# GPSGSMTruck.net
KiCad netlist of a schematic drawn in Altium Designer
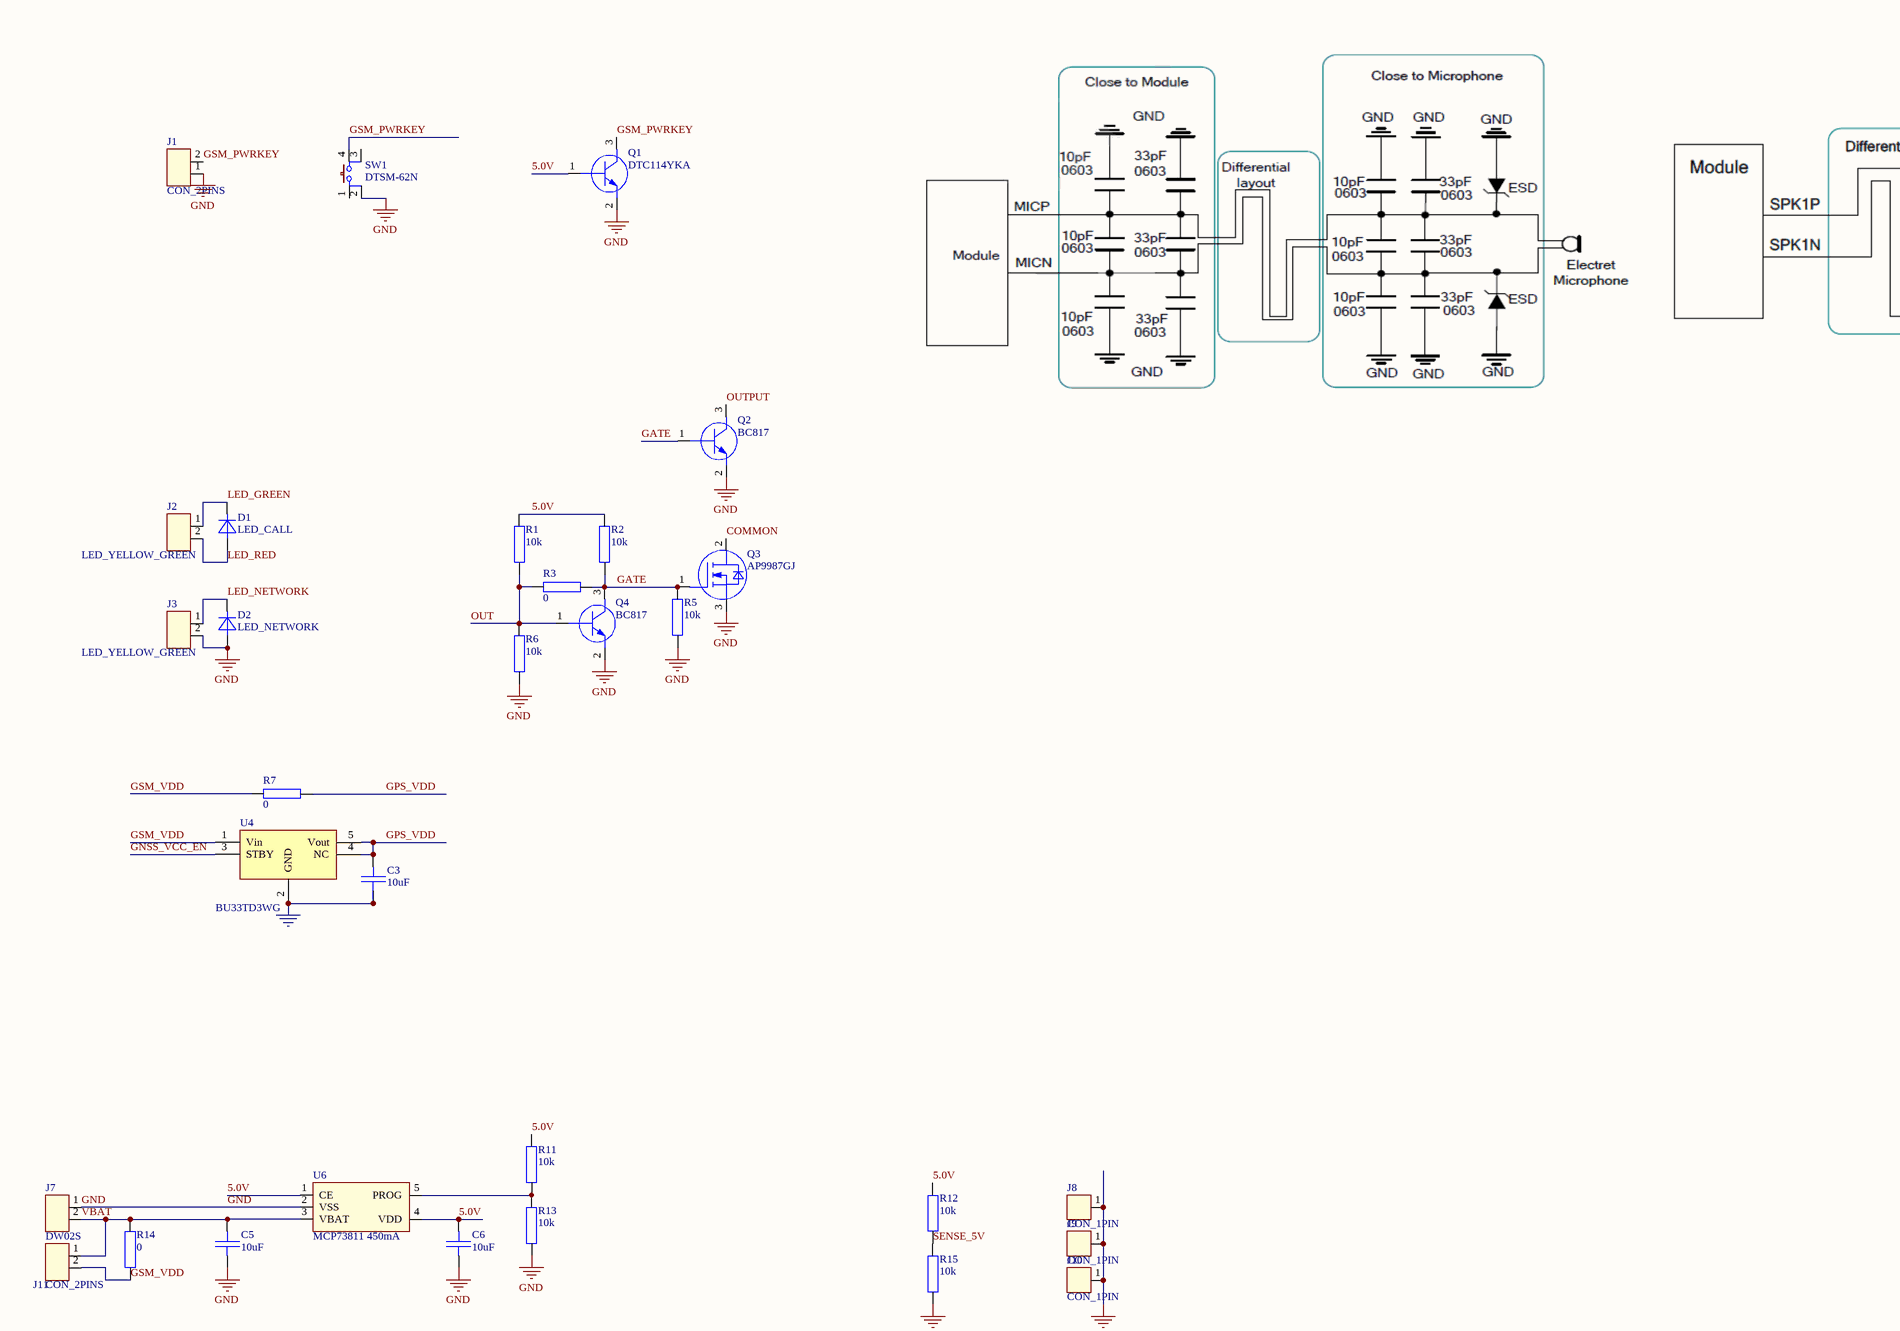
[diagram p0: GPSGSMTruck.SchDoc, top left]
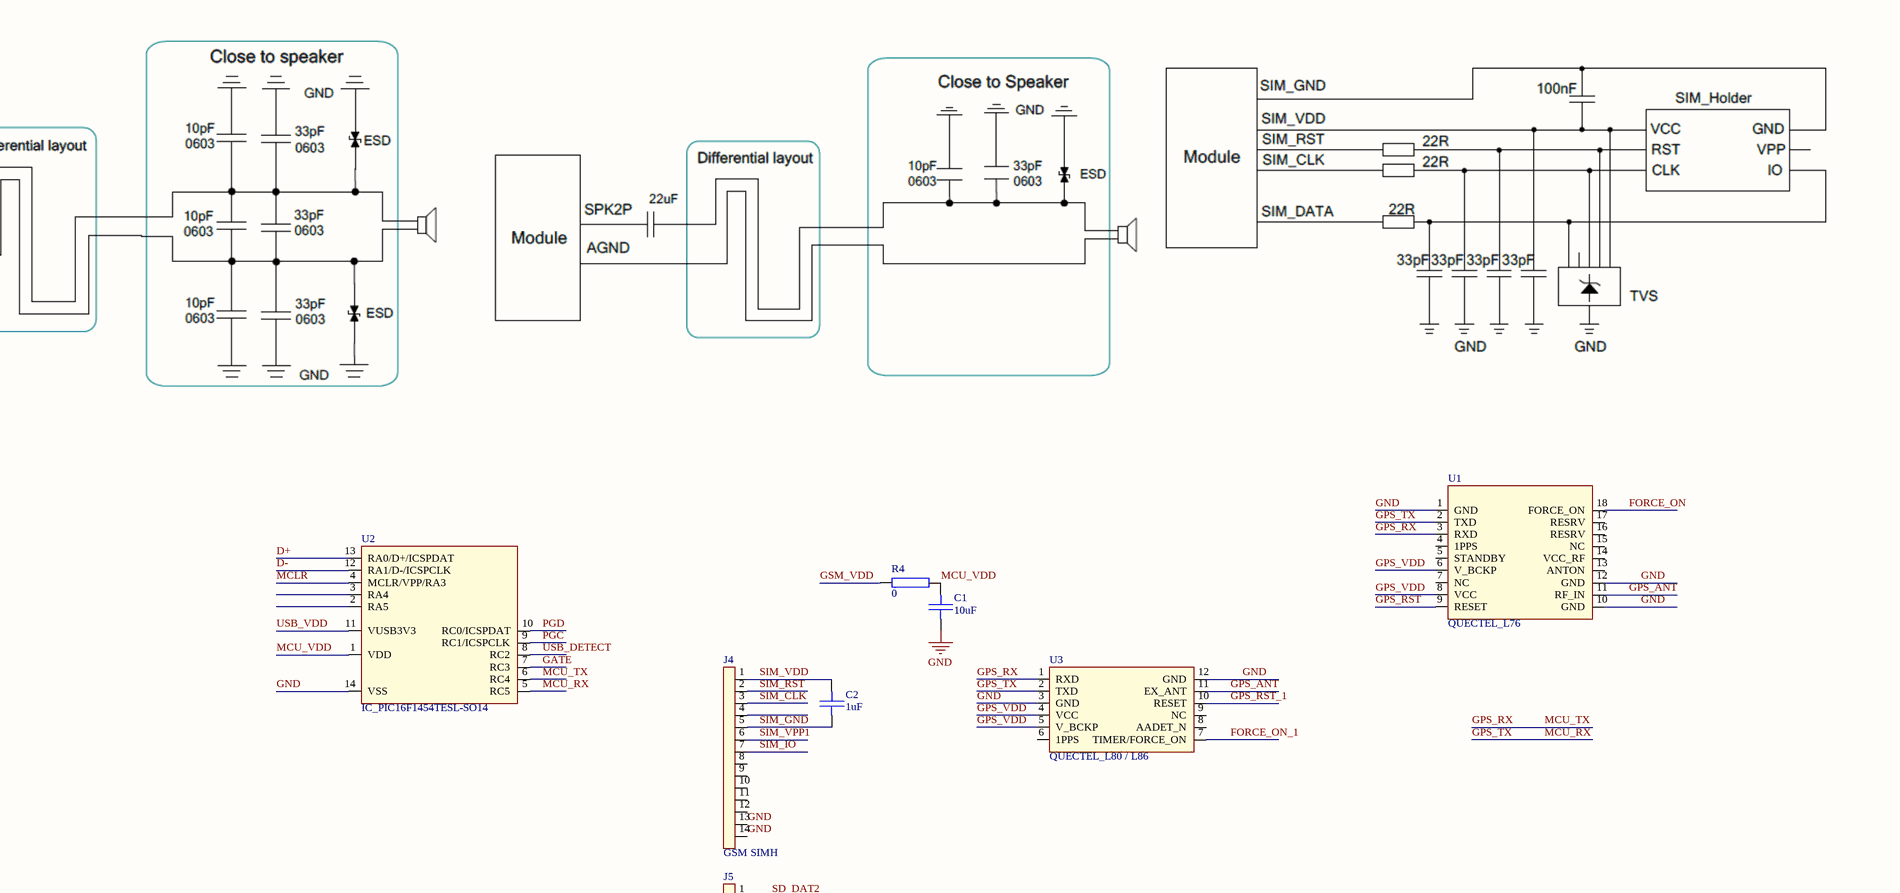
[diagram p1: GPSGSMTruck.SchDoc, top right]
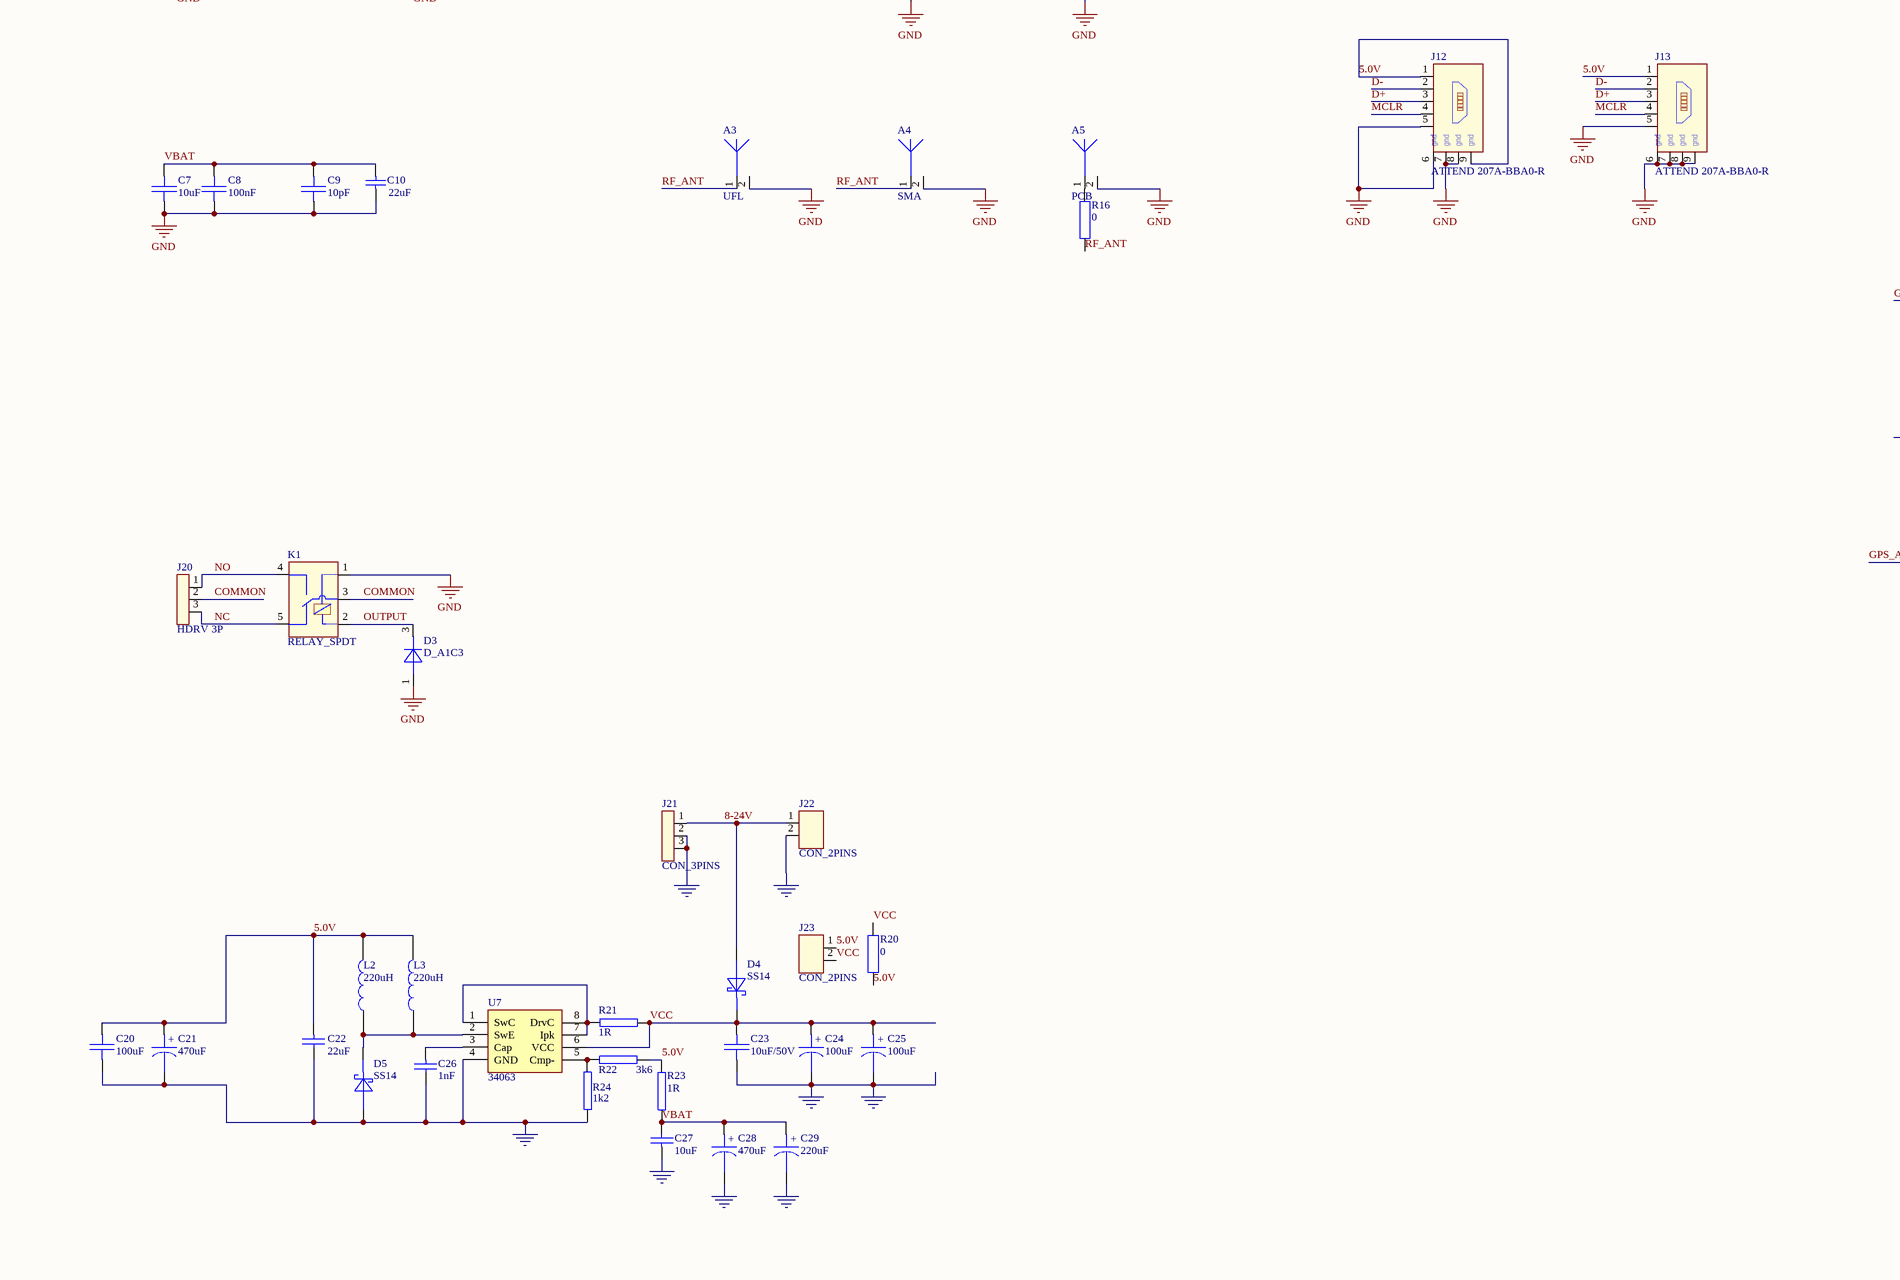
[diagram p2: GPSGSMTruck.SchDoc, bottom left]
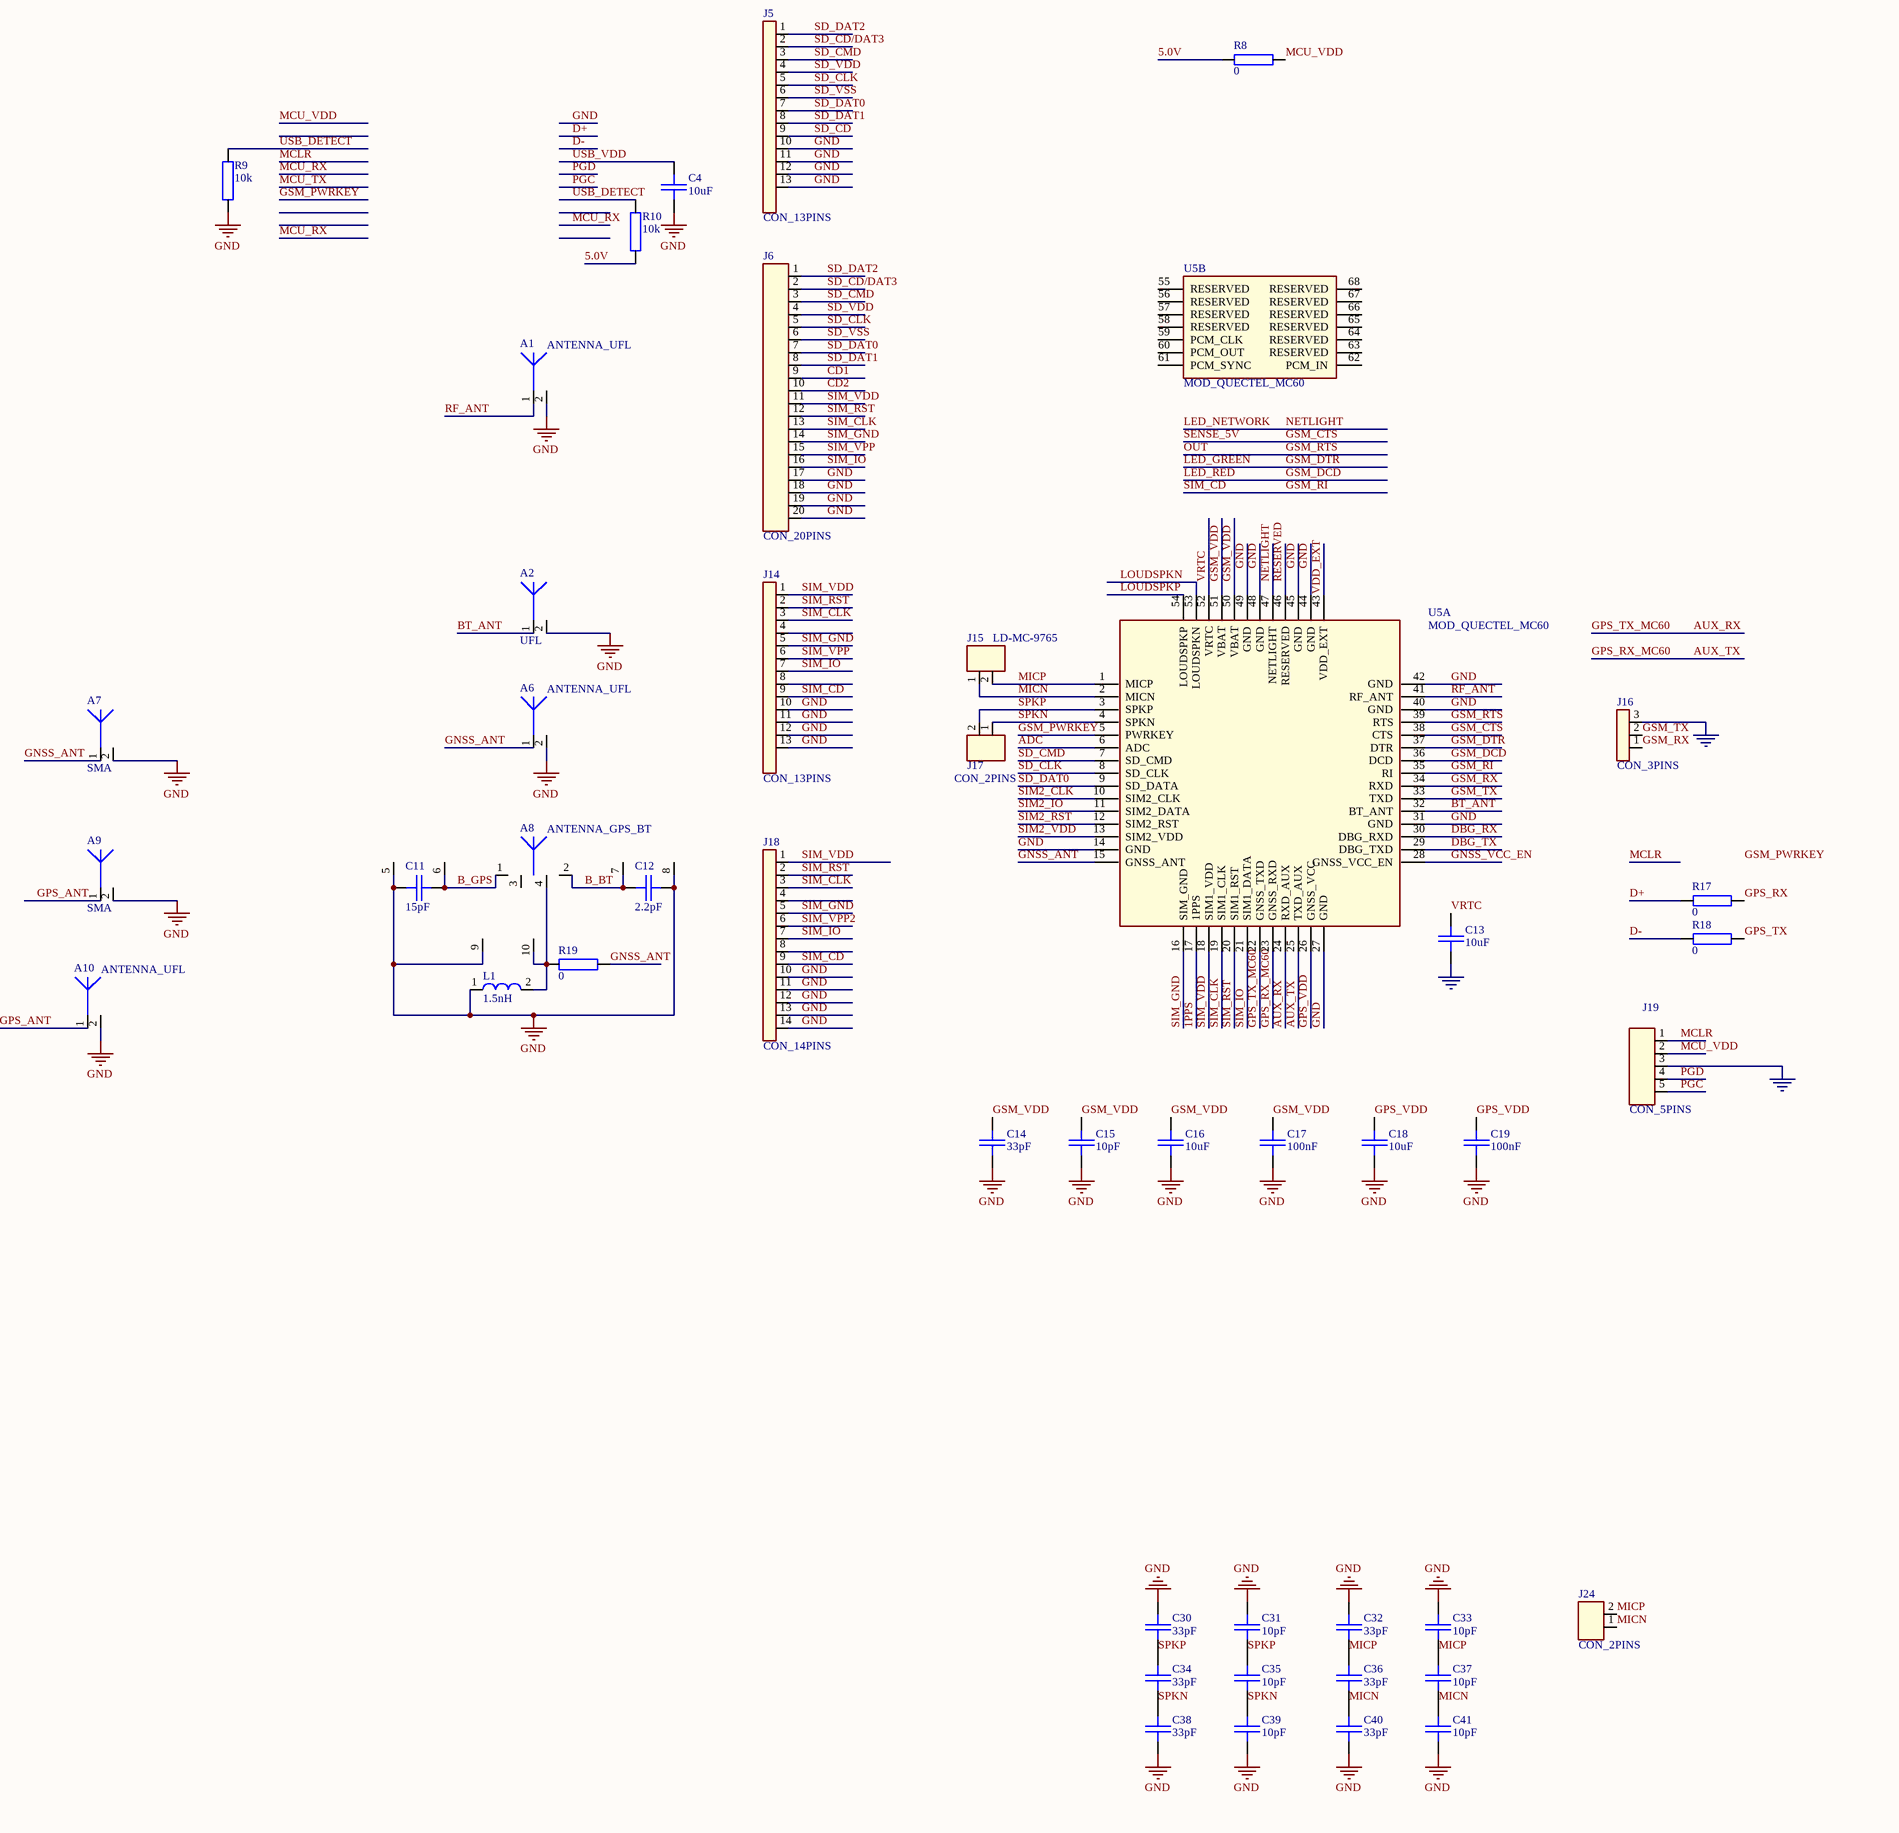
[diagram p3: GPSGSMTruck.SchDoc, bottom right]

(export (version "E")
  (design (tool "Eeschema 10.0.6"))
  (components
    (comp (ref "A1")
      (value "ANTENNA_UFL")
      (footprint "SMD_CON_ANTENNA_UFL")
      (libsource (lib "DLV") (part "ANTENNA_2"))
    )
    (comp (ref "A2")
      (value "UFL")
      (footprint "SMD_CON_ANTENNA_UFL")
      (libsource (lib "DLV") (part "ANTENNA_2"))
    )
    (comp (ref "A3")
      (value "UFL")
      (footprint "SMD_CON_ANTENNA_UFL")
      (libsource (lib "DLV") (part "ANTENNA_2"))
    )
    (comp (ref "A4")
      (value "SMA")
      (footprint "SMD_CON_ANTENNA_SMA_RIGHT_ANGLE")
      (libsource (lib "DLV") (part "ANTENNA_2"))
    )
    (comp (ref "A5")
      (value "PCB")
      (footprint "SMD_CON_ANTENNA_GSM_PCB_1_INV")
      (libsource (lib "DLV") (part "ANTENNA_2"))
    )
    (comp (ref "A6")
      (value "ANTENNA_UFL")
      (footprint "SMD_CON_ANTENNA_UFL")
      (libsource (lib "DLV") (part "ANTENNA_2"))
    )
    (comp (ref "A7")
      (value "SMA")
      (footprint "SMD_CON_ANTENNA_SMA_RIGHT_ANGLE")
      (libsource (lib "DLV") (part "ANTENNA_2"))
    )
    (comp (ref "A8")
      (value "ANTENNA_GPS_BT")
      (footprint "SMD_CHIP_ANTENNA_GPS_BT")
      (libsource (lib "DLV") (part "ANTENNA_GPS_BT"))
    )
    (comp (ref "A9")
      (value "SMA")
      (footprint "SMD_CON_ANTENNA_SMA_RIGHT_ANGLE")
      (libsource (lib "DLV") (part "ANTENNA_2"))
    )
    (comp (ref "A10")
      (value "ANTENNA_UFL")
      (footprint "SMD_CON_ANTENNA_UFL")
      (libsource (lib "DLV") (part "ANTENNA_2"))
    )
    (comp (ref "C1") (value "10uF") (footprint "SMD_0402_CAPC1005X90N") (libsource (lib "DLV") (part "C")))
    (comp (ref "C2") (value "1uF") (footprint "SMD_0603_CAPC1608X95N") (libsource (lib "DLV") (part "C")))
    (comp (ref "C3") (value "10uF") (footprint "SMD_0402_CAPC1005X90N") (libsource (lib "DLV") (part "C")))
    (comp (ref "C4") (value "10uF") (footprint "SMD_0402_CAPC1005X90N") (libsource (lib "DLV") (part "C")))
    (comp (ref "C5") (value "10uF") (footprint "SMD_0603_CAPC1608X95N") (libsource (lib "DLV") (part "C")))
    (comp (ref "C6") (value "10uF") (footprint "SMD_0603_CAPC1608X95N") (libsource (lib "DLV") (part "C")))
    (comp (ref "C7") (value "10uF") (footprint "SMD_0805_CAPC2012X95N") (libsource (lib "DLV") (part "C")))
    (comp (ref "C8") (value "100nF") (footprint "SMD_0603_CAPC1608X95N") (libsource (lib "DLV") (part "C")))
    (comp (ref "C9") (value "10pF") (footprint "SMD_0603_CAPC1608X95N") (libsource (lib "DLV") (part "C")))
    (comp (ref "C10")
      (value "22uF")
      (footprint "SMD_1210_CAPC3225X279N")
      (description "CL32A227MQVNNNE 220UF 6.3V 20% X5R 1210")
      (fields (field (name "PUBLISHER") "Altium Limited"))
      (libsource (lib "Miscellaneous Devices") (part "Cap Semi"))
    )
    (comp (ref "C11")
      (value "15pF")
      (footprint "SMD_0402_CAPC1005X90N - ANTENNA")
      (libsource (lib "DLV") (part "C"))
    )
    (comp (ref "C12")
      (value "2.2pF")
      (footprint "SMD_0201_CAPC0603X33N - ANTENNA")
      (libsource (lib "DLV") (part "C"))
    )
    (comp (ref "C13") (value "10uF") (footprint "SMD_0402_CAPC1005X90N") (libsource (lib "DLV") (part "C")))
    (comp (ref "C14") (value "33pF") (footprint "SMD_0402_CAPC1005X90N") (libsource (lib "DLV") (part "C")))
    (comp (ref "C15") (value "10pF") (footprint "SMD_0402_CAPC1005X90N") (libsource (lib "DLV") (part "C")))
    (comp (ref "C16") (value "10uF") (footprint "SMD_0402_CAPC1005X90N") (libsource (lib "DLV") (part "C")))
    (comp (ref "C17") (value "100nF") (footprint "SMD_0402_CAPC1005X90N") (libsource (lib "DLV") (part "C")))
    (comp (ref "C18") (value "10uF") (footprint "SMD_0402_CAPC1005X90N") (libsource (lib "DLV") (part "C")))
    (comp (ref "C19") (value "100nF") (footprint "SMD_0402_CAPC1005X90N") (libsource (lib "DLV") (part "C")))
    (comp (ref "C20") (value "100uF") (footprint "SMD_1210_CAPC3225X279N") (libsource (lib "DLV") (part "C")))
    (comp (ref "C21")
      (value "470uF")
      (footprint "PTH_CAPPR250-800X800")
      (description "Capacitor")
      (libsource (lib "*") (part "CAPACITOR POL"))
    )
    (comp (ref "C22")
      (value "22uF")
      (footprint "SMD_0805_CAPC2012X145N")
      (description "Capacitor")
      (libsource (lib "*") (part "CAP"))
    )
    (comp (ref "C23")
      (value "10uF/50V")
      (footprint "SMD_1210_CAPC3225X279N")
      (libsource (lib "DLV") (part "C"))
    )
    (comp (ref "C24")
      (value "100uF")
      (footprint "SMD_CAPAE660X550N")
      (description "Capacitor")
      (libsource (lib "*") (part "CAPACITOR POL"))
    )
    (comp (ref "C25")
      (value "100uF")
      (footprint "PTH_CAPPR250-800X800")
      (description "Capacitor")
      (libsource (lib "*") (part "CAPACITOR POL"))
    )
    (comp (ref "C26")
      (value "1nF")
      (footprint "SMD_0603_CAPC1608X95N")
      (description "Capacitor")
      (libsource (lib "*") (part "CAP"))
    )
    (comp (ref "C27")
      (value "10uF")
      (footprint "SMD_0603_CAPC1608X95N")
      (description "Capacitor")
      (libsource (lib "*") (part "CAP"))
    )
    (comp (ref "C28")
      (value "470uF")
      (footprint "PTH_CAPPR250-800X800")
      (description "Capacitor")
      (libsource (lib "*") (part "CAPACITOR POL"))
    )
    (comp (ref "C29")
      (value "220uF")
      (footprint "SMD_CAPAE660X550N")
      (description "Capacitor")
      (libsource (lib "*") (part "CAPACITOR POL"))
    )
    (comp (ref "C30") (value "33pF") (footprint "SMD_0603_CAPC1608X95N") (libsource (lib "DLV") (part "C")))
    (comp (ref "C31") (value "10pF") (footprint "SMD_0603_CAPC1608X95N") (libsource (lib "DLV") (part "C")))
    (comp (ref "C32") (value "33pF") (footprint "SMD_0603_CAPC1608X95N") (libsource (lib "DLV") (part "C")))
    (comp (ref "C33") (value "10pF") (footprint "SMD_0603_CAPC1608X95N") (libsource (lib "DLV") (part "C")))
    (comp (ref "C34") (value "33pF") (footprint "SMD_0603_CAPC1608X95N") (libsource (lib "DLV") (part "C")))
    (comp (ref "C35") (value "10pF") (footprint "SMD_0603_CAPC1608X95N") (libsource (lib "DLV") (part "C")))
    (comp (ref "C36") (value "33pF") (footprint "SMD_0603_CAPC1608X95N") (libsource (lib "DLV") (part "C")))
    (comp (ref "C37") (value "10pF") (footprint "SMD_0603_CAPC1608X95N") (libsource (lib "DLV") (part "C")))
    (comp (ref "C38") (value "33pF") (footprint "SMD_0603_CAPC1608X95N") (libsource (lib "DLV") (part "C")))
    (comp (ref "C39") (value "10pF") (footprint "SMD_0603_CAPC1608X95N") (libsource (lib "DLV") (part "C")))
    (comp (ref "C40") (value "33pF") (footprint "SMD_0603_CAPC1608X95N") (libsource (lib "DLV") (part "C")))
    (comp (ref "C41") (value "10pF") (footprint "SMD_0603_CAPC1608X95N") (libsource (lib "DLV") (part "C")))
    (comp (ref "D1")
      (value "LED_CALL")
      (footprint "SMD_0805_LED2012X100N")
      (libsource (lib "DLV") (part "D"))
    )
    (comp (ref "D2")
      (value "LED_NETWORK")
      (footprint "SMD_0805_LED2012X100N")
      (libsource (lib "DLV") (part "D"))
    )
    (comp (ref "D3")
      (value "D_A1C3")
      (footprint "SMD_SOT23_SOT95P240X120-3N")
      (description "1N4148")
      (libsource (lib "DLV") (part "D_A1C3"))
    )
    (comp (ref "D4") (value "SS14") (footprint "SMD_DO214AC_SMA") (libsource (lib "BitCoin") (part "D_STKY")))
    (comp (ref "D5") (value "SS14") (footprint "SMD_DO214AC_SMA") (libsource (lib "BitCoin") (part "D_STKY")))
    (comp (ref "J1")
      (value "CON_2PINS")
      (footprint "PTH_HDRV02W64P254_1X02")
      (libsource (lib "") (part "CON_2PINS_2"))
    )
    (comp (ref "J2")
      (value "LED_YELLOW_GREEN")
      (footprint "PTH_LED-KINGBRIGHT-L-934SGC")
      (libsource (lib "DLV") (part "CON_2PINS"))
    )
    (comp (ref "J3")
      (value "LED_YELLOW_GREEN")
      (footprint "PTH_LED-KINGBRIGHT-L-934SGC")
      (libsource (lib "DLV") (part "CON_2PINS"))
    )
    (comp (ref "J4")
      (value "GSM SIMH")
      (footprint "SMD_CON-ATTEND_SIM_115B-AAA0-R01")
      (libsource (lib "DLV") (part "CON_14PINS"))
    )
    (comp (ref "J5") (value "CON_13PINS") (footprint "NONE") (libsource (lib "DLV") (part "CON_13PINS")))
    (comp (ref "J6") (value "CON_20PINS") (footprint "NONE") (libsource (lib "DLV") (part "CON_20PINS")))
    (comp (ref "J7")
      (value "DW02S")
      (footprint "PTH_HDRV02W64P254_1X02_BATTERY")
      (libsource (lib "DLV") (part "CON_2PINS"))
    )
    (comp (ref "J8")
      (value "CON_1PIN")
      (footprint "PTH_MOUNT_HOLE")
      (libsource (lib "DLV") (part "CON_1PIN"))
    )
    (comp (ref "J9")
      (value "CON_1PIN")
      (footprint "PTH_MOUNT_HOLE")
      (libsource (lib "DLV") (part "CON_1PIN"))
    )
    (comp (ref "J10")
      (value "CON_1PIN")
      (footprint "PTH_MOUNT_HOLE")
      (libsource (lib "DLV") (part "CON_1PIN"))
    )
    (comp (ref "J11")
      (value "CON_2PINS")
      (footprint "PTH_HDRV02W64P254_1X02")
      (libsource (lib "DLV") (part "CON_2PINS"))
    )
    (comp (ref "J12")
      (value "ATTEND 207A-BBA0-R")
      (footprint "SMD_CON_MICRO_USB")
      (libsource (lib "DLV") (part "CON_USB_MINI"))
    )
    (comp (ref "J13")
      (value "ATTEND 207A-BBA0-R")
      (footprint "SMD_CON-CVILUX-CU04-SCM15B0")
      (libsource (lib "DLV") (part "CON_USB_MINI"))
    )
    (comp (ref "J14")
      (value "CON_13PINS")
      (footprint "SMD_CON-ATTEND_MICRO_SIM_115Q-BCA0")
      (libsource (lib "DLV") (part "CON_13PINS"))
    )
    (comp (ref "J15")
      (value "LD-MC-9765")
      (footprint "PTH_MIC_9.6MM_6MM")
      (libsource (lib "") (part "CON_2PINS_3"))
    )
    (comp (ref "J16")
      (value "CON_3PINS")
      (footprint "PTH_HDRV03W64P254_1X03")
      (libsource (lib "DLV") (part "CON_3PINS"))
    )
    (comp (ref "J17")
      (value "CON_2PINS")
      (footprint "PTH_MIC_6MM_2.7MM_PITCH1.9")
      (libsource (lib "DLV") (part "CON_2PINS"))
    )
    (comp (ref "J18") (value "CON_14PINS") (footprint "NONE") (libsource (lib "DLV") (part "CON_14PINS")))
    (comp (ref "J19") (value "CON_5PINS") (footprint "SIP5 - PGM") (libsource (lib "DLV") (part "CON_5PINS")))
    (comp (ref "J20")
      (value "HDRV 3P")
      (footprint "PTH_HDRV03W11060P500_1X03")
      (libsource (lib "") (part "CON_3PINS_1"))
    )
    (comp (ref "J21")
      (value "CON_3PINS")
      (footprint "PTH_DC-POWER-JACK_210-112")
      (libsource (lib "") (part "CON_3PINS_1"))
    )
    (comp (ref "J22")
      (value "CON_2PINS")
      (footprint "PTH_HDRV02W11060P350_1X02")
      (libsource (lib "") (part "CON_2PINS_1"))
    )
    (comp (ref "J23")
      (value "CON_2PINS")
      (footprint "PTH_HDRV02W64P254_1X02")
      (libsource (lib "DLV") (part "CON_2PINS"))
    )
    (comp (ref "J24")
      (value "CON_2PINS")
      (footprint "PTH_MIC_6MM_2.7MM_PITCH1.9")
      (libsource (lib "") (part "CON_2PINS_2"))
    )
    (comp (ref "K1")
      (value "RELAY_SPDT")
      (footprint "PTH_REL_RAS")
      (libsource (lib "DLV") (part "RELAY_SPDT"))
    )
    (comp (ref "L1")
      (value "1.5nH")
      (footprint "SMD_0402_INDC1005X55N - ANTENNA")
      (libsource (lib "DLV") (part "L"))
    )
    (comp (ref "L2")
      (value "220uH")
      (footprint "SMD_INDM600500")
      (description "FPI0504 DA54")
      (libsource (lib "Miscellaneous Devices") (part "INDUCTOR1"))
    )
    (comp (ref "L3")
      (value "220uH")
      (footprint "PTH_CAPPR250-800X800")
      (libsource (lib "Miscellaneous Devices") (part "INDUCTOR1"))
    )
    (comp (ref "Q1")
      (value "DTC114YKA")
      (footprint "SMD_SOT23_SOT95P240X120-3N")
      (libsource (lib "DLV") (part "BJT_NPN_B1E2C3"))
    )
    (comp (ref "Q2")
      (value "BC817")
      (footprint "SMD_SOT23_SOT95P240X120-3N")
      (libsource (lib "DLV") (part "BJT_NPN_B1E2C3"))
    )
    (comp (ref "Q3")
      (value "AP9987GJ")
      (footprint "PTH_TO220AB")
      (libsource (lib "DLV") (part "MOS_N_D1_G1D2S3"))
    )
    (comp (ref "Q4")
      (value "BC817")
      (footprint "SMD_SOT23_SOT95P240X120-3N")
      (libsource (lib "DLV") (part "BJT_NPN_B1E2C3"))
    )
    (comp (ref "R1") (value "10k") (footprint "SMD_0603_RESC1608X55N") (libsource (lib "DLV") (part "R")))
    (comp (ref "R2") (value "10k") (footprint "SMD_0603_RESC1608X55N") (libsource (lib "DLV") (part "R")))
    (comp (ref "R3") (value "0") (footprint "SMD_0603_RESC1608X55N") (libsource (lib "DLV") (part "R")))
    (comp (ref "R4") (value "0") (footprint "SMD_0402_RESC1005X37N") (libsource (lib "DLV") (part "R")))
    (comp (ref "R5") (value "10k") (footprint "SMD_0603_RESC1608X55N") (libsource (lib "DLV") (part "R")))
    (comp (ref "R6") (value "10k") (footprint "SMD_0603_RESC1608X55N") (libsource (lib "DLV") (part "R")))
    (comp (ref "R7") (value "0") (footprint "SMD_0402_RESC1005X37N") (libsource (lib "DLV") (part "R")))
    (comp (ref "R8") (value "0") (footprint "SMD_0402_RESC1005X37N") (libsource (lib "DLV") (part "R")))
    (comp (ref "R9") (value "10k") (footprint "SMD_0402_RESC1005X37N") (libsource (lib "DLV") (part "R")))
    (comp (ref "R10") (value "10k") (footprint "SMD_0402_RESC1005X37N") (libsource (lib "DLV") (part "R")))
    (comp (ref "R11") (value "10k") (footprint "SMD_0603_RESC1608X55N") (libsource (lib "DLV") (part "R")))
    (comp (ref "R12") (value "10k") (footprint "SMD_0603_RESC1608X55N") (libsource (lib "DLV") (part "R")))
    (comp (ref "R13") (value "10k") (footprint "SMD_0603_RESC1608X55N") (libsource (lib "DLV") (part "R")))
    (comp (ref "R14") (value "0") (footprint "SMD_0603_RESC1608X55N") (libsource (lib "DLV") (part "R")))
    (comp (ref "R15") (value "10k") (footprint "SMD_0603_RESC1608X55N") (libsource (lib "DLV") (part "R")))
    (comp (ref "R16") (value "0") (footprint "SMD_0402_RESC1005X37N") (libsource (lib "DLV") (part "R")))
    (comp (ref "R17") (value "0") (footprint "SMD_0402_RESC1005X37N") (libsource (lib "DLV") (part "R")))
    (comp (ref "R18") (value "0") (footprint "SMD_0402_RESC1005X37N") (libsource (lib "DLV") (part "R")))
    (comp (ref "R19") (value "0") (footprint "SMD_0402_RESC1005X37N") (libsource (lib "DLV") (part "R")))
    (comp (ref "R20") (value "0") (footprint "SMD_0603_RESC1608X55N") (libsource (lib "DLV") (part "R")))
    (comp (ref "R21")
      (value "1R")
      (footprint "SMD_0805_RESC2012X60N")
      (libsource (lib "Miscellaneous Devices") (part "RES2"))
    )
    (comp (ref "R22")
      (value "3k6")
      (footprint "SMD_0603_RESC1608X55N")
      (libsource (lib "Miscellaneous Devices") (part "RES2"))
    )
    (comp (ref "R23")
      (value "1R")
      (footprint "SMD_0603_RESC1608X55N")
      (libsource (lib "Miscellaneous Devices") (part "RES2"))
    )
    (comp (ref "R24")
      (value "1k2")
      (footprint "SMD_0603_RESC1608X55N")
      (libsource (lib "Miscellaneous Devices") (part "RES2"))
    )
    (comp (ref "SW1")
      (value "DTSM-62N")
      (footprint "SMD_SW_TACT-64K_5")
      (libsource (lib "DLV") (part "BUTTON_1"))
    )
    (comp (ref "U1")
      (value "QUECTEL_L76")
      (footprint "SMD_MOD_L76_SOIC110P970X1010-18N")
      (libsource (lib "DLV") (part "MOD_QUECTEL_L76"))
    )
    (comp (ref "U2")
      (value "IC_PIC16F1454TESL-SO14")
      (footprint "SMD_SOIC127P600X175-14N")
      (libsource (lib "DLV") (part "IC_PIC16F1454TESL-SO14"))
    )
    (comp (ref "U3")
      (value "QUECTEL_L80 / L86")
      (footprint "SMD_MOD_L80_SOIC254P1600X1600-12N")
      (libsource (lib "DLV") (part "MOD_QUECTEL_L80_L86"))
    )
    (comp (ref "U4")
      (value "BU33TD3WG")
      (footprint "SMD_SOT26_SOT95P285X140-5N - DLV")
      (libsource (lib "DLV") (part "IC_BU33TD3WG"))
    )
    (comp (ref "U5")
      (value "MOD_QUECTEL_MC60")
      (footprint "SMD_MOD_MC60_54_PIN")
      (libsource (lib "DLV") (part "MOD_QUECTEL_MC60"))
    )
    (comp (ref "U6")
      (value "MCP73811 450mA")
      (footprint "SMD_SOT26_SOT95P285X140-5N - DLV")
      (description "MCP73812")
      (fields
        (field (name "DB_PART_NUMBER") "PSU000000127")
        (field (name "DB_MANUFACTURER_PART") "ROHM        BD33KA5WF-E2")
        (field (name "DB_APPROVED_BY") "VSN")
      )
      (libsource (lib "DLV") (part "IC_MCP73812"))
    )
    (comp (ref "U7")
      (value "34063")
      (footprint "SMD_SOIC127P600X175-8N")
      (description "DC/DC converter")
      (libsource (lib "Devices") (part "34063"))
    )
  )
  (nets
    (net (code "1") (name "/1PPS") (class "Default")
      (node (ref "U5") (pin "17") (pinfunction "1PPS_17") (pintype "passive"))
    )
    (net (code "2") (name "/5.0V") (class "Default")
      (node (ref "C20") (pin "2") (pinfunction "2_2") (pintype "passive"))
      (node (ref "C21") (pin "1") (pinfunction "1_1") (pintype "passive"))
      (node (ref "C22") (pin "1") (pinfunction "1_1") (pintype "passive"))
      (node (ref "C6") (pin "1") (pinfunction "1_1") (pintype "passive"))
      (node (ref "J12") (pin "1") (pinfunction "1_1") (pintype "passive"))
      (node (ref "J12") (pin "9") (pinfunction "9_9") (pintype "passive"))
      (node (ref "J13") (pin "1") (pinfunction "1_1") (pintype "passive"))
      (node (ref "J23") (pin "1") (pinfunction "1_1") (pintype "passive"))
      (node (ref "L2") (pin "2") (pinfunction "2_2") (pintype "passive"))
      (node (ref "L3") (pin "2") (pinfunction "2_2") (pintype "passive"))
      (node (ref "Q1") (pin "1") (pinfunction "B_1") (pintype "passive"))
      (node (ref "R1") (pin "1") (pinfunction "1_1") (pintype "passive"))
      (node (ref "R10") (pin "2") (pinfunction "2_2") (pintype "passive"))
      (node (ref "R11") (pin "1") (pinfunction "1_1") (pintype "passive"))
      (node (ref "R12") (pin "1") (pinfunction "1_1") (pintype "passive"))
      (node (ref "R2") (pin "1") (pinfunction "1_1") (pintype "passive"))
      (node (ref "R20") (pin "2") (pinfunction "2_2") (pintype "passive"))
      (node (ref "R22") (pin "1") (pinfunction "1_1") (pintype "passive"))
      (node (ref "R23") (pin "2") (pinfunction "2_2") (pintype "passive"))
      (node (ref "R8") (pin "1") (pinfunction "1_1") (pintype "passive"))
      (node (ref "U6") (pin "1") (pinfunction "CE_1") (pintype "passive"))
      (node (ref "U6") (pin "4") (pinfunction "VDD_4") (pintype "passive"))
    )
    (net (code "3") (name "/8-24V") (class "Default")
      (node (ref "D4") (pin "2") (pinfunction "A_2") (pintype "passive"))
      (node (ref "J21") (pin "1") (pinfunction "1_1") (pintype "passive"))
      (node (ref "J22") (pin "1") (pinfunction "1_1") (pintype "passive"))
    )
    (net (code "4") (name "/ADC") (class "Default")
      (node (ref "U5") (pin "6") (pinfunction "ADC_6") (pintype "passive"))
    )
    (net (code "5") (name "/AUX_RX") (class "Default")
      (node (ref "U5") (pin "22") (pinfunction "GNSS_TXD_22") (pintype "passive"))
      (node (ref "U5") (pin "24") (pinfunction "RXD_AUX_24") (pintype "passive"))
    )
    (net (code "6") (name "/AUX_TX") (class "Default")
      (node (ref "U5") (pin "23") (pinfunction "GNSS_RXD_23") (pintype "passive"))
      (node (ref "U5") (pin "25") (pinfunction "TXD_AUX_25") (pintype "passive"))
    )
    (net (code "7") (name "/BT_ANT") (class "Default")
      (node (ref "A2") (pin "1") (pinfunction "1_1") (pintype "passive"))
      (node (ref "U5") (pin "32") (pinfunction "BT_ANT_32") (pintype "passive"))
    )
    (net (code "8") (name "/B_BT") (class "Default")
      (node (ref "A8") (pin "2") (pinfunction "2_2") (pintype "passive"))
      (node (ref "A8") (pin "7") (pinfunction "7_7") (pintype "passive"))
      (node (ref "C12") (pin "1") (pinfunction "1_1") (pintype "passive"))
    )
    (net (code "9") (name "/B_GPS") (class "Default")
      (node (ref "A8") (pin "1") (pinfunction "1_1") (pintype "passive"))
      (node (ref "A8") (pin "6") (pinfunction "6_6") (pintype "passive"))
      (node (ref "C11") (pin "2") (pinfunction "2_2") (pintype "passive"))
    )
    (net (code "10") (name "/CD1") (class "Default")
      (node (ref "J6") (pin "9") (pinfunction "9_9") (pintype "passive"))
    )
    (net (code "11") (name "/CD2") (class "Default")
      (node (ref "J6") (pin "10") (pinfunction "10_10") (pintype "passive"))
    )
    (net (code "12") (name "/COMMON") (class "Default")
      (node (ref "J20") (pin "2") (pinfunction "2_2") (pintype "passive"))
      (node (ref "K1") (pin "3") (pinfunction "3_3") (pintype "passive"))
      (node (ref "Q3") (pin "2") (pinfunction "D_2") (pintype "passive"))
    )
    (net (code "13") (name "/D+") (class "Default")
      (node (ref "J12") (pin "3") (pinfunction "3_3") (pintype "passive"))
      (node (ref "J13") (pin "3") (pinfunction "3_3") (pintype "passive"))
      (node (ref "R17") (pin "1") (pinfunction "1_1") (pintype "passive"))
      (node (ref "U2") (pin "13") (pinfunction "RA0/D+/ICSPDAT_13") (pintype "passive"))
    )
    (net (code "14") (name "/D-") (class "Default")
      (node (ref "J12") (pin "2") (pinfunction "2_2") (pintype "passive"))
      (node (ref "J13") (pin "2") (pinfunction "2_2") (pintype "passive"))
      (node (ref "R18") (pin "1") (pinfunction "1_1") (pintype "passive"))
      (node (ref "U2") (pin "12") (pinfunction "RA1/D-/ICSPCLK_12") (pintype "passive"))
    )
    (net (code "15") (name "/DBG_RX") (class "Default")
      (node (ref "U5") (pin "30") (pinfunction "DBG_RXD_30") (pintype "passive"))
    )
    (net (code "16") (name "/DBG_TX") (class "Default")
      (node (ref "U5") (pin "29") (pinfunction "DBG_TXD_29") (pintype "passive"))
    )
    (net (code "17") (name "/FORCE_ON") (class "Default")
      (node (ref "U1") (pin "18") (pinfunction "FORCE_ON_18") (pintype "passive"))
    )
    (net (code "18") (name "/FORCE_ON_1") (class "Default")
      (node (ref "U3") (pin "7") (pinfunction "TIMER/FORCE_ON_7") (pintype "passive"))
    )
    (net (code "19") (name "/GATE") (class "Default")
      (node (ref "Q2") (pin "1") (pinfunction "B_1") (pintype "passive"))
      (node (ref "Q3") (pin "1") (pinfunction "G_1") (pintype "passive"))
      (node (ref "Q4") (pin "3") (pinfunction "C_3") (pintype "passive"))
      (node (ref "R2") (pin "2") (pinfunction "2_2") (pintype "passive"))
      (node (ref "R3") (pin "2") (pinfunction "2_2") (pintype "passive"))
      (node (ref "R5") (pin "1") (pinfunction "1_1") (pintype "passive"))
      (node (ref "U2") (pin "7") (pinfunction "RC3_7") (pintype "passive"))
    )
    (net (code "20") (name "/GNSS_ANT") (class "Default")
      (node (ref "A6") (pin "1") (pinfunction "1_1") (pintype "passive"))
      (node (ref "A7") (pin "1") (pinfunction "1_1") (pintype "passive"))
      (node (ref "R19") (pin "1") (pinfunction "1_1") (pintype "passive"))
      (node (ref "U5") (pin "15") (pinfunction "GNSS_ANT_15") (pintype "passive"))
    )
    (net (code "21") (name "/GNSS_VCC_EN") (class "Default")
      (node (ref "U4") (pin "3") (pinfunction "STBY_3") (pintype "passive"))
      (node (ref "U5") (pin "28") (pinfunction "GNSS_VCC_EN_28") (pintype "passive"))
    )
    (net (code "22") (name "/GPS_ANT") (class "Default")
      (node (ref "A10") (pin "1") (pinfunction "1_1") (pintype "passive"))
      (node (ref "A9") (pin "1") (pinfunction "1_1") (pintype "passive"))
      (node (ref "U1") (pin "11") (pinfunction "RF_IN_11") (pintype "passive"))
      (node (ref "U3") (pin "11") (pinfunction "EX_ANT_11") (pintype "passive"))
    )
    (net (code "23") (name "/GPS_RST") (class "Default")
      (node (ref "U1") (pin "9") (pinfunction "RESET_9") (pintype "passive"))
    )
    (net (code "24") (name "/GPS_RST_1") (class "Default")
      (node (ref "U3") (pin "10") (pinfunction "RESET_10") (pintype "passive"))
    )
    (net (code "25") (name "/GPS_RX") (class "Default")
      (node (ref "R17") (pin "2") (pinfunction "2_2") (pintype "passive"))
      (node (ref "U1") (pin "3") (pinfunction "RXD_3") (pintype "passive"))
      (node (ref "U2") (pin "6") (pinfunction "RC4_6") (pintype "passive"))
      (node (ref "U3") (pin "1") (pinfunction "RXD_1") (pintype "passive"))
    )
    (net (code "26") (name "/GPS_TX") (class "Default")
      (node (ref "R18") (pin "2") (pinfunction "2_2") (pintype "passive"))
      (node (ref "U1") (pin "2") (pinfunction "TXD_2") (pintype "passive"))
      (node (ref "U2") (pin "5") (pinfunction "RC5_5") (pintype "passive"))
      (node (ref "U3") (pin "2") (pinfunction "TXD_2") (pintype "passive"))
    )
    (net (code "27") (name "/GPS_VDD") (class "Default")
      (node (ref "C18") (pin "1") (pinfunction "1_1") (pintype "passive"))
      (node (ref "C19") (pin "1") (pinfunction "1_1") (pintype "passive"))
      (node (ref "C3") (pin "1") (pinfunction "1_1") (pintype "passive"))
      (node (ref "R7") (pin "2") (pinfunction "2_2") (pintype "passive"))
      (node (ref "U1") (pin "6") (pinfunction "V_BCKP_6") (pintype "passive"))
      (node (ref "U1") (pin "8") (pinfunction "VCC_8") (pintype "passive"))
      (node (ref "U3") (pin "4") (pinfunction "VCC_4") (pintype "passive"))
      (node (ref "U3") (pin "5") (pinfunction "V_BCKP_5") (pintype "passive"))
      (node (ref "U4") (pin "4") (pinfunction "NC_4") (pintype "passive"))
      (node (ref "U4") (pin "5") (pinfunction "Vout_5") (pintype "passive"))
      (node (ref "U5") (pin "26") (pinfunction "GNSS_VCC_26") (pintype "passive"))
    )
    (net (code "28") (name "/GSM_CTS") (class "Default")
      (node (ref "R12") (pin "2") (pinfunction "2_2") (pintype "passive"))
      (node (ref "R15") (pin "1") (pinfunction "1_1") (pintype "passive"))
      (node (ref "U5") (pin "38") (pinfunction "CTS_38") (pintype "passive"))
    )
    (net (code "29") (name "/GSM_DCD") (class "Default")
      (node (ref "D1") (pin "2") (pinfunction "A_2") (pintype "passive"))
      (node (ref "J2") (pin "2") (pinfunction "2_2") (pintype "passive"))
      (node (ref "U5") (pin "36") (pinfunction "DCD_36") (pintype "passive"))
    )
    (net (code "30") (name "/GSM_DTR") (class "Default")
      (node (ref "D1") (pin "1") (pinfunction "C_1") (pintype "passive"))
      (node (ref "J2") (pin "1") (pinfunction "1_1") (pintype "passive"))
      (node (ref "U5") (pin "37") (pinfunction "DTR_37") (pintype "passive"))
    )
    (net (code "31") (name "/GSM_PWRKEY") (class "Default")
      (node (ref "J1") (pin "2") (pinfunction "2_2") (pintype "passive"))
      (node (ref "Q1") (pin "3") (pinfunction "C_3") (pintype "passive"))
      (node (ref "SW1") (pin "4") (pinfunction "4_4") (pintype "passive"))
      (node (ref "U5") (pin "5") (pinfunction "PWRKEY_5") (pintype "passive"))
    )
    (net (code "32") (name "/GSM_RI") (class "Default")
      (node (ref "J14") (pin "9") (pinfunction "9_9") (pintype "passive"))
      (node (ref "J18") (pin "9") (pinfunction "9_9") (pintype "passive"))
      (node (ref "U5") (pin "35") (pinfunction "RI_35") (pintype "passive"))
    )
    (net (code "33") (name "/GSM_RTS") (class "Default")
      (node (ref "Q4") (pin "1") (pinfunction "B_1") (pintype "passive"))
      (node (ref "R1") (pin "2") (pinfunction "2_2") (pintype "passive"))
      (node (ref "R3") (pin "1") (pinfunction "1_1") (pintype "passive"))
      (node (ref "R6") (pin "1") (pinfunction "1_1") (pintype "passive"))
      (node (ref "U5") (pin "39") (pinfunction "RTS_39") (pintype "passive"))
    )
    (net (code "34") (name "/GSM_RX") (class "Default")
      (node (ref "J16") (pin "1") (pinfunction "1_1") (pintype "passive"))
      (node (ref "U5") (pin "34") (pinfunction "RXD_34") (pintype "passive"))
    )
    (net (code "35") (name "/GSM_TX") (class "Default")
      (node (ref "J16") (pin "2") (pinfunction "2_2") (pintype "passive"))
      (node (ref "U5") (pin "33") (pinfunction "TXD_33") (pintype "passive"))
    )
    (net (code "36") (name "/GSM_VDD") (class "Default")
      (node (ref "C14") (pin "1") (pinfunction "1_1") (pintype "passive"))
      (node (ref "C15") (pin "1") (pinfunction "1_1") (pintype "passive"))
      (node (ref "C16") (pin "1") (pinfunction "1_1") (pintype "passive"))
      (node (ref "C17") (pin "1") (pinfunction "1_1") (pintype "passive"))
      (node (ref "J11") (pin "2") (pinfunction "2_2") (pintype "passive"))
      (node (ref "R14") (pin "1") (pinfunction "1_1") (pintype "passive"))
      (node (ref "R4") (pin "1") (pinfunction "1_1") (pintype "passive"))
      (node (ref "R7") (pin "1") (pinfunction "1_1") (pintype "passive"))
      (node (ref "U4") (pin "1") (pinfunction "Vin_1") (pintype "passive"))
      (node (ref "U5") (pin "50") (pinfunction "VBAT_50") (pintype "passive"))
      (node (ref "U5") (pin "51") (pinfunction "VBAT_51") (pintype "passive"))
    )
    (net (code "37") (name "/LED_NETWORK") (class "Default")
      (node (ref "D2") (pin "1") (pinfunction "C_1") (pintype "passive"))
      (node (ref "J3") (pin "1") (pinfunction "1_1") (pintype "passive"))
      (node (ref "U5") (pin "47") (pinfunction "NETLIGHT_47") (pintype "passive"))
    )
    (net (code "38") (name "/LOUDSPKN") (class "Default")
      (node (ref "U5") (pin "53") (pinfunction "LOUDSPKN_53") (pintype "passive"))
    )
    (net (code "39") (name "/LOUDSPKP") (class "Default")
      (node (ref "U5") (pin "54") (pinfunction "LOUDSPKP_54") (pintype "passive"))
    )
    (net (code "40") (name "/MCLR") (class "Default")
      (node (ref "J12") (pin "4") (pinfunction "4_4") (pintype "passive"))
      (node (ref "J13") (pin "4") (pinfunction "4_4") (pintype "passive"))
      (node (ref "J19") (pin "1") (pinfunction "1_1") (pintype "passive"))
      (node (ref "U2") (pin "4") (pinfunction "MCLR/VPP/RA3_4") (pintype "passive"))
    )
    (net (code "41") (name "/MCU_VDD") (class "Default")
      (node (ref "C1") (pin "1") (pinfunction "1_1") (pintype "passive"))
      (node (ref "J19") (pin "2") (pinfunction "2_2") (pintype "passive"))
      (node (ref "R4") (pin "2") (pinfunction "2_2") (pintype "passive"))
      (node (ref "R8") (pin "2") (pinfunction "2_2") (pintype "passive"))
      (node (ref "U2") (pin "1") (pinfunction "VDD_1") (pintype "passive"))
    )
    (net (code "42") (name "/MICN") (class "Default")
      (node (ref "C36") (pin "2") (pinfunction "2_2") (pintype "passive"))
      (node (ref "C37") (pin "2") (pinfunction "2_2") (pintype "passive"))
      (node (ref "C40") (pin "1") (pinfunction "1_1") (pintype "passive"))
      (node (ref "C41") (pin "1") (pinfunction "1_1") (pintype "passive"))
      (node (ref "J15") (pin "1") (pinfunction "1_1") (pintype "passive"))
      (node (ref "J24") (pin "1") (pinfunction "1_1") (pintype "passive"))
      (node (ref "U5") (pin "2") (pinfunction "MICN_2") (pintype "passive"))
    )
    (net (code "43") (name "/MICP") (class "Default")
      (node (ref "C32") (pin "2") (pinfunction "2_2") (pintype "passive"))
      (node (ref "C33") (pin "2") (pinfunction "2_2") (pintype "passive"))
      (node (ref "C36") (pin "1") (pinfunction "1_1") (pintype "passive"))
      (node (ref "C37") (pin "1") (pinfunction "1_1") (pintype "passive"))
      (node (ref "J15") (pin "2") (pinfunction "2_2") (pintype "passive"))
      (node (ref "J24") (pin "2") (pinfunction "2_2") (pintype "passive"))
      (node (ref "U5") (pin "1") (pinfunction "MICP_1") (pintype "passive"))
    )
    (net (code "44") (name "/NC") (class "Default")
      (node (ref "J20") (pin "3") (pinfunction "3_3") (pintype "passive"))
      (node (ref "K1") (pin "5") (pinfunction "5_5") (pintype "passive"))
    )
    (net (code "45") (name "/NO") (class "Default")
      (node (ref "J20") (pin "1") (pinfunction "1_1") (pintype "passive"))
      (node (ref "K1") (pin "4") (pinfunction "4_4") (pintype "passive"))
    )
    (net (code "46") (name "/OUTPUT") (class "Default")
      (node (ref "D3") (pin "3") (pinfunction "C_3") (pintype "passive"))
      (node (ref "K1") (pin "2") (pinfunction "2_2") (pintype "passive"))
      (node (ref "Q2") (pin "3") (pinfunction "C_3") (pintype "passive"))
    )
    (net (code "47") (name "/PGC") (class "Default")
      (node (ref "J19") (pin "5") (pinfunction "5_5") (pintype "passive"))
      (node (ref "U2") (pin "9") (pinfunction "RC1/ICSPCLK_9") (pintype "passive"))
    )
    (net (code "48") (name "/PGD") (class "Default")
      (node (ref "J19") (pin "4") (pinfunction "4_4") (pintype "passive"))
      (node (ref "U2") (pin "10") (pinfunction "RC0/ICSPDAT_10") (pintype "passive"))
    )
    (net (code "49") (name "/RESERVED") (class "Default")
      (node (ref "U5") (pin "46") (pinfunction "RESERVED_46") (pintype "passive"))
    )
    (net (code "50") (name "/RF_ANT") (class "Default")
      (node (ref "A1") (pin "1") (pinfunction "1_1") (pintype "passive"))
      (node (ref "A3") (pin "1") (pinfunction "1_1") (pintype "passive"))
      (node (ref "A4") (pin "1") (pinfunction "1_1") (pintype "passive"))
      (node (ref "R16") (pin "2") (pinfunction "2_2") (pintype "passive"))
      (node (ref "U5") (pin "41") (pinfunction "RF_ANT_41") (pintype "passive"))
    )
    (net (code "51") (name "/SD_CD") (class "Default")
      (node (ref "J5") (pin "9") (pinfunction "9_9") (pintype "passive"))
    )
    (net (code "52") (name "/SD_CD{slash}DAT3") (class "Default")
      (node (ref "J5") (pin "2") (pinfunction "2_2") (pintype "passive"))
      (node (ref "J6") (pin "2") (pinfunction "2_2") (pintype "passive"))
    )
    (net (code "53") (name "/SD_CLK") (class "Default")
      (node (ref "J5") (pin "5") (pinfunction "5_5") (pintype "passive"))
      (node (ref "J6") (pin "5") (pinfunction "5_5") (pintype "passive"))
      (node (ref "U5") (pin "8") (pinfunction "SD_CLK_8") (pintype "passive"))
    )
    (net (code "54") (name "/SD_CMD") (class "Default")
      (node (ref "J5") (pin "3") (pinfunction "3_3") (pintype "passive"))
      (node (ref "J6") (pin "3") (pinfunction "3_3") (pintype "passive"))
      (node (ref "U5") (pin "7") (pinfunction "SD_CMD_7") (pintype "passive"))
    )
    (net (code "55") (name "/SD_DAT0") (class "Default")
      (node (ref "J5") (pin "7") (pinfunction "7_7") (pintype "passive"))
      (node (ref "J6") (pin "7") (pinfunction "7_7") (pintype "passive"))
      (node (ref "U5") (pin "9") (pinfunction "SD_DATA_9") (pintype "passive"))
    )
    (net (code "56") (name "/SD_DAT1") (class "Default")
      (node (ref "J5") (pin "8") (pinfunction "8_8") (pintype "passive"))
      (node (ref "J6") (pin "8") (pinfunction "8_8") (pintype "passive"))
    )
    (net (code "57") (name "/SD_DAT2") (class "Default")
      (node (ref "J5") (pin "1") (pinfunction "1_1") (pintype "passive"))
      (node (ref "J6") (pin "1") (pinfunction "1_1") (pintype "passive"))
    )
    (net (code "58") (name "/SD_VDD") (class "Default")
      (node (ref "J5") (pin "4") (pinfunction "4_4") (pintype "passive"))
      (node (ref "J6") (pin "4") (pinfunction "4_4") (pintype "passive"))
    )
    (net (code "59") (name "/SD_VSS") (class "Default")
      (node (ref "J5") (pin "6") (pinfunction "6_6") (pintype "passive"))
      (node (ref "J6") (pin "6") (pinfunction "6_6") (pintype "passive"))
    )
    (net (code "60") (name "/SIM2_CLK") (class "Default")
      (node (ref "U5") (pin "10") (pinfunction "SIM2_CLK_10") (pintype "passive"))
    )
    (net (code "61") (name "/SIM2_IO") (class "Default")
      (node (ref "U5") (pin "11") (pinfunction "SIM2_DATA_11") (pintype "passive"))
    )
    (net (code "62") (name "/SIM2_RST") (class "Default")
      (node (ref "U5") (pin "12") (pinfunction "SIM2_RST_12") (pintype "passive"))
    )
    (net (code "63") (name "/SIM2_VDD") (class "Default")
      (node (ref "U5") (pin "13") (pinfunction "SIM2_VDD_13") (pintype "passive"))
    )
    (net (code "64") (name "/SIM_CLK") (class "Default")
      (node (ref "J14") (pin "3") (pinfunction "3_3") (pintype "passive"))
      (node (ref "J18") (pin "3") (pinfunction "3_3") (pintype "passive"))
      (node (ref "J4") (pin "3") (pinfunction "3_3") (pintype "passive"))
      (node (ref "J6") (pin "13") (pinfunction "13_13") (pintype "passive"))
      (node (ref "U5") (pin "19") (pinfunction "SIM1_CLK_19") (pintype "passive"))
    )
    (net (code "65") (name "/SIM_GND") (class "Default")
      (node (ref "C2") (pin "2") (pinfunction "2_2") (pintype "passive"))
      (node (ref "J14") (pin "5") (pinfunction "5_5") (pintype "passive"))
      (node (ref "J18") (pin "5") (pinfunction "5_5") (pintype "passive"))
      (node (ref "J4") (pin "5") (pinfunction "5_5") (pintype "passive"))
      (node (ref "J6") (pin "14") (pinfunction "14_14") (pintype "passive"))
      (node (ref "U5") (pin "16") (pinfunction "SIM_GND_16") (pintype "passive"))
    )
    (net (code "66") (name "/SIM_IO") (class "Default")
      (node (ref "J14") (pin "7") (pinfunction "7_7") (pintype "passive"))
      (node (ref "J18") (pin "7") (pinfunction "7_7") (pintype "passive"))
      (node (ref "J4") (pin "7") (pinfunction "7_7") (pintype "passive"))
      (node (ref "J6") (pin "16") (pinfunction "16_16") (pintype "passive"))
      (node (ref "U5") (pin "21") (pinfunction "SIM1_DATA_21") (pintype "passive"))
    )
    (net (code "67") (name "/SIM_RST") (class "Default")
      (node (ref "J14") (pin "2") (pinfunction "2_2") (pintype "passive"))
      (node (ref "J18") (pin "2") (pinfunction "2_2") (pintype "passive"))
      (node (ref "J4") (pin "2") (pinfunction "2_2") (pintype "passive"))
      (node (ref "J6") (pin "12") (pinfunction "12_12") (pintype "passive"))
      (node (ref "U5") (pin "20") (pinfunction "SIM1_RST_20") (pintype "passive"))
    )
    (net (code "68") (name "/SIM_VDD") (class "Default")
      (node (ref "C2") (pin "1") (pinfunction "1_1") (pintype "passive"))
      (node (ref "J14") (pin "1") (pinfunction "1_1") (pintype "passive"))
      (node (ref "J18") (pin "1") (pinfunction "1_1") (pintype "passive"))
      (node (ref "J4") (pin "1") (pinfunction "1_1") (pintype "passive"))
      (node (ref "J6") (pin "11") (pinfunction "11_11") (pintype "passive"))
      (node (ref "U5") (pin "18") (pinfunction "SIM1_VDD_18") (pintype "passive"))
    )
    (net (code "69") (name "/SIM_VPP") (class "Default")
      (node (ref "J14") (pin "6") (pinfunction "6_6") (pintype "passive"))
      (node (ref "J6") (pin "15") (pinfunction "15_15") (pintype "passive"))
    )
    (net (code "70") (name "/SIM_VPP1") (class "Default")
      (node (ref "J4") (pin "6") (pinfunction "6_6") (pintype "passive"))
    )
    (net (code "71") (name "/SIM_VPP2") (class "Default")
      (node (ref "J18") (pin "6") (pinfunction "6_6") (pintype "passive"))
    )
    (net (code "72") (name "/SPKN") (class "Default")
      (node (ref "C34") (pin "2") (pinfunction "2_2") (pintype "passive"))
      (node (ref "C35") (pin "2") (pinfunction "2_2") (pintype "passive"))
      (node (ref "C38") (pin "1") (pinfunction "1_1") (pintype "passive"))
      (node (ref "C39") (pin "1") (pinfunction "1_1") (pintype "passive"))
      (node (ref "J17") (pin "1") (pinfunction "1_1") (pintype "passive"))
      (node (ref "U5") (pin "4") (pinfunction "SPKN_4") (pintype "passive"))
    )
    (net (code "73") (name "/SPKP") (class "Default")
      (node (ref "C30") (pin "2") (pinfunction "2_2") (pintype "passive"))
      (node (ref "C31") (pin "2") (pinfunction "2_2") (pintype "passive"))
      (node (ref "C34") (pin "1") (pinfunction "1_1") (pintype "passive"))
      (node (ref "C35") (pin "1") (pinfunction "1_1") (pintype "passive"))
      (node (ref "J17") (pin "2") (pinfunction "2_2") (pintype "passive"))
      (node (ref "U5") (pin "3") (pinfunction "SPKP_3") (pintype "passive"))
    )
    (net (code "74") (name "/USB_DETECT") (class "Default")
      (node (ref "R10") (pin "1") (pinfunction "1_1") (pintype "passive"))
      (node (ref "R9") (pin "2") (pinfunction "2_2") (pintype "passive"))
      (node (ref "U2") (pin "8") (pinfunction "RC2_8") (pintype "passive"))
    )
    (net (code "75") (name "/USB_VDD") (class "Default")
      (node (ref "C4") (pin "1") (pinfunction "1_1") (pintype "passive"))
      (node (ref "U2") (pin "11") (pinfunction "VUSB3V3_11") (pintype "passive"))
    )
    (net (code "76") (name "/VBAT") (class "Default")
      (node (ref "C10") (pin "1") (pinfunction "1_1") (pintype "passive"))
      (node (ref "C27") (pin "2") (pinfunction "2_2") (pintype "passive"))
      (node (ref "C28") (pin "1") (pinfunction "1_1") (pintype "passive"))
      (node (ref "C29") (pin "1") (pinfunction "1_1") (pintype "passive"))
      (node (ref "C5") (pin "1") (pinfunction "1_1") (pintype "passive"))
      (node (ref "C7") (pin "1") (pinfunction "1_1") (pintype "passive"))
      (node (ref "C8") (pin "1") (pinfunction "1_1") (pintype "passive"))
      (node (ref "C9") (pin "1") (pinfunction "1_1") (pintype "passive"))
      (node (ref "J11") (pin "1") (pinfunction "1_1") (pintype "passive"))
      (node (ref "J7") (pin "2") (pinfunction "2_2") (pintype "passive"))
      (node (ref "R14") (pin "2") (pinfunction "2_2") (pintype "passive"))
      (node (ref "R23") (pin "1") (pinfunction "1_1") (pintype "passive"))
      (node (ref "U6") (pin "3") (pinfunction "VBAT_3") (pintype "passive"))
    )
    (net (code "77") (name "/VCC") (class "Default")
      (node (ref "C23") (pin "2") (pinfunction "2_2") (pintype "passive"))
      (node (ref "C24") (pin "1") (pinfunction "1_1") (pintype "passive"))
      (node (ref "C25") (pin "1") (pinfunction "1_1") (pintype "passive"))
      (node (ref "D4") (pin "1") (pinfunction "C_1") (pintype "passive"))
      (node (ref "J23") (pin "2") (pinfunction "2_2") (pintype "passive"))
      (node (ref "R20") (pin "1") (pinfunction "1_1") (pintype "passive"))
      (node (ref "R21") (pin "2") (pinfunction "2_2") (pintype "passive"))
      (node (ref "U7") (pin "6") (pinfunction "VCC_6") (pintype "passive"))
    )
    (net (code "78") (name "/VDD_EXT") (class "Default")
      (node (ref "U5") (pin "43") (pinfunction "VDD_EXT_43") (pintype "passive"))
    )
    (net (code "79") (name "/VRTC") (class "Default")
      (node (ref "C13") (pin "1") (pinfunction "1_1") (pintype "passive"))
      (node (ref "U5") (pin "52") (pinfunction "VRTC_52") (pintype "passive"))
    )
    (net (code "80") (name "GND") (class "Default")
      (node (ref "A1") (pin "2") (pinfunction "2_2") (pintype "passive"))
      (node (ref "A10") (pin "2") (pinfunction "2_2") (pintype "passive"))
      (node (ref "A2") (pin "2") (pinfunction "2_2") (pintype "passive"))
      (node (ref "A3") (pin "2") (pinfunction "2_2") (pintype "passive"))
      (node (ref "A4") (pin "2") (pinfunction "2_2") (pintype "passive"))
      (node (ref "A5") (pin "2") (pinfunction "2_2") (pintype "passive"))
      (node (ref "A6") (pin "2") (pinfunction "2_2") (pintype "passive"))
      (node (ref "A7") (pin "2") (pinfunction "2_2") (pintype "passive"))
      (node (ref "A8") (pin "5") (pinfunction "5_5") (pintype "passive"))
      (node (ref "A8") (pin "8") (pinfunction "8_8") (pintype "passive"))
      (node (ref "A8") (pin "9") (pinfunction "9_9") (pintype "passive"))
      (node (ref "A9") (pin "2") (pinfunction "2_2") (pintype "passive"))
      (node (ref "C1") (pin "2") (pinfunction "2_2") (pintype "passive"))
      (node (ref "C10") (pin "2") (pinfunction "2_2") (pintype "passive"))
      (node (ref "C11") (pin "1") (pinfunction "1_1") (pintype "passive"))
      (node (ref "C12") (pin "2") (pinfunction "2_2") (pintype "passive"))
      (node (ref "C13") (pin "2") (pinfunction "2_2") (pintype "passive"))
      (node (ref "C14") (pin "2") (pinfunction "2_2") (pintype "passive"))
      (node (ref "C15") (pin "2") (pinfunction "2_2") (pintype "passive"))
      (node (ref "C16") (pin "2") (pinfunction "2_2") (pintype "passive"))
      (node (ref "C17") (pin "2") (pinfunction "2_2") (pintype "passive"))
      (node (ref "C18") (pin "2") (pinfunction "2_2") (pintype "passive"))
      (node (ref "C19") (pin "2") (pinfunction "2_2") (pintype "passive"))
      (node (ref "C20") (pin "1") (pinfunction "1_1") (pintype "passive"))
      (node (ref "C21") (pin "2") (pinfunction "2_2") (pintype "passive"))
      (node (ref "C22") (pin "2") (pinfunction "2_2") (pintype "passive"))
      (node (ref "C23") (pin "1") (pinfunction "1_1") (pintype "passive"))
      (node (ref "C24") (pin "2") (pinfunction "2_2") (pintype "passive"))
      (node (ref "C25") (pin "2") (pinfunction "2_2") (pintype "passive"))
      (node (ref "C26") (pin "2") (pinfunction "2_2") (pintype "passive"))
      (node (ref "C27") (pin "1") (pinfunction "1_1") (pintype "passive"))
      (node (ref "C28") (pin "2") (pinfunction "2_2") (pintype "passive"))
      (node (ref "C29") (pin "2") (pinfunction "2_2") (pintype "passive"))
      (node (ref "C3") (pin "2") (pinfunction "2_2") (pintype "passive"))
      (node (ref "C30") (pin "1") (pinfunction "1_1") (pintype "passive"))
      (node (ref "C31") (pin "1") (pinfunction "1_1") (pintype "passive"))
      (node (ref "C32") (pin "1") (pinfunction "1_1") (pintype "passive"))
      (node (ref "C33") (pin "1") (pinfunction "1_1") (pintype "passive"))
      (node (ref "C38") (pin "2") (pinfunction "2_2") (pintype "passive"))
      (node (ref "C39") (pin "2") (pinfunction "2_2") (pintype "passive"))
      (node (ref "C4") (pin "2") (pinfunction "2_2") (pintype "passive"))
      (node (ref "C40") (pin "2") (pinfunction "2_2") (pintype "passive"))
      (node (ref "C41") (pin "2") (pinfunction "2_2") (pintype "passive"))
      (node (ref "C5") (pin "2") (pinfunction "2_2") (pintype "passive"))
      (node (ref "C6") (pin "2") (pinfunction "2_2") (pintype "passive"))
      (node (ref "C7") (pin "2") (pinfunction "2_2") (pintype "passive"))
      (node (ref "C8") (pin "2") (pinfunction "2_2") (pintype "passive"))
      (node (ref "C9") (pin "2") (pinfunction "2_2") (pintype "passive"))
      (node (ref "D2") (pin "2") (pinfunction "A_2") (pintype "passive"))
      (node (ref "D3") (pin "1") (pinfunction "A_1") (pintype "passive"))
      (node (ref "D5") (pin "2") (pinfunction "A_2") (pintype "passive"))
      (node (ref "J1") (pin "1") (pinfunction "1_1") (pintype "passive"))
      (node (ref "J10") (pin "1") (pinfunction "1_1") (pintype "passive"))
      (node (ref "J12") (pin "5") (pinfunction "5_5") (pintype "passive"))
      (node (ref "J12") (pin "6") (pinfunction "6_6") (pintype "passive"))
      (node (ref "J12") (pin "7") (pinfunction "7_7") (pintype "passive"))
      (node (ref "J12") (pin "8") (pinfunction "8_8") (pintype "passive"))
      (node (ref "J13") (pin "5") (pinfunction "5_5") (pintype "passive"))
      (node (ref "J13") (pin "6") (pinfunction "6_6") (pintype "passive"))
      (node (ref "J13") (pin "7") (pinfunction "7_7") (pintype "passive"))
      (node (ref "J13") (pin "8") (pinfunction "8_8") (pintype "passive"))
      (node (ref "J13") (pin "9") (pinfunction "9_9") (pintype "passive"))
      (node (ref "J14") (pin "10") (pinfunction "10_10") (pintype "passive"))
      (node (ref "J14") (pin "11") (pinfunction "11_11") (pintype "passive"))
      (node (ref "J14") (pin "12") (pinfunction "12_12") (pintype "passive"))
      (node (ref "J14") (pin "13") (pinfunction "13_13") (pintype "passive"))
      (node (ref "J16") (pin "3") (pinfunction "3_3") (pintype "passive"))
      (node (ref "J18") (pin "10") (pinfunction "10_10") (pintype "passive"))
      (node (ref "J18") (pin "11") (pinfunction "11_11") (pintype "passive"))
      (node (ref "J18") (pin "12") (pinfunction "12_12") (pintype "passive"))
      (node (ref "J18") (pin "13") (pinfunction "13_13") (pintype "passive"))
      (node (ref "J18") (pin "14") (pinfunction "14_14") (pintype "passive"))
      (node (ref "J19") (pin "3") (pinfunction "3_3") (pintype "passive"))
      (node (ref "J21") (pin "2") (pinfunction "2_2") (pintype "passive"))
      (node (ref "J21") (pin "3") (pinfunction "3_3") (pintype "passive"))
      (node (ref "J22") (pin "2") (pinfunction "2_2") (pintype "passive"))
      (node (ref "J3") (pin "2") (pinfunction "2_2") (pintype "passive"))
      (node (ref "J4") (pin "13") (pinfunction "13_13") (pintype "passive"))
      (node (ref "J4") (pin "14") (pinfunction "14_14") (pintype "passive"))
      (node (ref "J5") (pin "10") (pinfunction "10_10") (pintype "passive"))
      (node (ref "J5") (pin "11") (pinfunction "11_11") (pintype "passive"))
      (node (ref "J5") (pin "12") (pinfunction "12_12") (pintype "passive"))
      (node (ref "J5") (pin "13") (pinfunction "13_13") (pintype "passive"))
      (node (ref "J6") (pin "17") (pinfunction "17_17") (pintype "passive"))
      (node (ref "J6") (pin "18") (pinfunction "18_18") (pintype "passive"))
      (node (ref "J6") (pin "19") (pinfunction "19_19") (pintype "passive"))
      (node (ref "J6") (pin "20") (pinfunction "20_20") (pintype "passive"))
      (node (ref "J7") (pin "1") (pinfunction "1_1") (pintype "passive"))
      (node (ref "J8") (pin "1") (pinfunction "1_1") (pintype "passive"))
      (node (ref "J9") (pin "1") (pinfunction "1_1") (pintype "passive"))
      (node (ref "K1") (pin "1") (pinfunction "1_1") (pintype "passive"))
      (node (ref "L1") (pin "1") (pinfunction "1_1") (pintype "passive"))
      (node (ref "Q1") (pin "2") (pinfunction "E_2") (pintype "passive"))
      (node (ref "Q2") (pin "2") (pinfunction "E_2") (pintype "passive"))
      (node (ref "Q3") (pin "3") (pinfunction "S_3") (pintype "passive"))
      (node (ref "Q4") (pin "2") (pinfunction "E_2") (pintype "passive"))
      (node (ref "R13") (pin "2") (pinfunction "2_2") (pintype "passive"))
      (node (ref "R15") (pin "2") (pinfunction "2_2") (pintype "passive"))
      (node (ref "R24") (pin "2") (pinfunction "2_2") (pintype "passive"))
      (node (ref "R5") (pin "2") (pinfunction "2_2") (pintype "passive"))
      (node (ref "R6") (pin "2") (pinfunction "2_2") (pintype "passive"))
      (node (ref "R9") (pin "1") (pinfunction "1_1") (pintype "passive"))
      (node (ref "SW1") (pin "2") (pinfunction "2_2") (pintype "passive"))
      (node (ref "U1") (pin "1") (pinfunction "GND_1") (pintype "passive"))
      (node (ref "U1") (pin "10") (pinfunction "GND_10") (pintype "passive"))
      (node (ref "U1") (pin "12") (pinfunction "GND_12") (pintype "passive"))
      (node (ref "U2") (pin "14") (pinfunction "VSS_14") (pintype "passive"))
      (node (ref "U3") (pin "12") (pinfunction "GND_12") (pintype "passive"))
      (node (ref "U3") (pin "3") (pinfunction "GND_3") (pintype "passive"))
      (node (ref "U4") (pin "2") (pinfunction "GND_2") (pintype "passive"))
      (node (ref "U5") (pin "14") (pinfunction "GND_14") (pintype "passive"))
      (node (ref "U5") (pin "27") (pinfunction "GND_27") (pintype "passive"))
      (node (ref "U5") (pin "31") (pinfunction "GND_31") (pintype "passive"))
      (node (ref "U5") (pin "40") (pinfunction "GND_40") (pintype "passive"))
      (node (ref "U5") (pin "42") (pinfunction "GND_42") (pintype "passive"))
      (node (ref "U5") (pin "44") (pinfunction "GND_44") (pintype "passive"))
      (node (ref "U5") (pin "45") (pinfunction "GND_45") (pintype "passive"))
      (node (ref "U5") (pin "48") (pinfunction "GND_48") (pintype "passive"))
      (node (ref "U5") (pin "49") (pinfunction "GND_49") (pintype "passive"))
      (node (ref "U6") (pin "2") (pinfunction "VSS_2") (pintype "passive"))
      (node (ref "U7") (pin "4") (pinfunction "GND_4") (pintype "passive"))
    )
    (net (code "81") (name "Net-(A5-Pad1)") (class "Default")
      (node (ref "A5") (pin "1") (pinfunction "1_1") (pintype "passive"))
      (node (ref "R16") (pin "1") (pinfunction "1_1") (pintype "passive"))
    )
    (net (code "82") (name "Net-(A8-Pad10)") (class "Default")
      (node (ref "A8") (pin "10") (pinfunction "10_10") (pintype "passive"))
      (node (ref "A8") (pin "4") (pinfunction "4_4") (pintype "passive"))
      (node (ref "L1") (pin "2") (pinfunction "2_2") (pintype "passive"))
      (node (ref "R19") (pin "2") (pinfunction "2_2") (pintype "passive"))
    )
    (net (code "83") (name "Net-(D5-C)") (class "Default")
      (node (ref "D5") (pin "1") (pinfunction "C_1") (pintype "passive"))
      (node (ref "L2") (pin "1") (pinfunction "1_1") (pintype "passive"))
      (node (ref "L3") (pin "1") (pinfunction "1_1") (pintype "passive"))
      (node (ref "U7") (pin "2") (pinfunction "SwE_2") (pintype "passive"))
    )
    (net (code "84") (name "Net-(U6-PROG)") (class "Default")
      (node (ref "R11") (pin "2") (pinfunction "2_2") (pintype "passive"))
      (node (ref "R13") (pin "1") (pinfunction "1_1") (pintype "passive"))
      (node (ref "U6") (pin "5") (pinfunction "PROG_5") (pintype "passive"))
    )
    (net (code "85") (name "Net-(U7-Cap)") (class "Default")
      (node (ref "C26") (pin "1") (pinfunction "1_1") (pintype "passive"))
      (node (ref "U7") (pin "3") (pinfunction "Cap_3") (pintype "passive"))
    )
    (net (code "86") (name "Net-(U7-Cmp-)") (class "Default")
      (node (ref "R22") (pin "2") (pinfunction "2_2") (pintype "passive"))
      (node (ref "R24") (pin "1") (pinfunction "1_1") (pintype "passive"))
      (node (ref "U7") (pin "5") (pinfunction "Cmp-_5") (pintype "passive"))
    )
    (net (code "87") (name "Net-(U7-DrvC)") (class "Default")
      (node (ref "R21") (pin "1") (pinfunction "1_1") (pintype "passive"))
      (node (ref "U7") (pin "1") (pinfunction "SwC_1") (pintype "passive"))
      (node (ref "U7") (pin "7") (pinfunction "Ipk_7") (pintype "passive"))
      (node (ref "U7") (pin "8") (pinfunction "DrvC_8") (pintype "passive"))
    )
    (net (code "88") (name "unconnected-(A8-Pad3)") (class "Default")
      (node (ref "A8") (pin "3") (pinfunction "3_3") (pintype "passive"))
    )
    (net (code "89") (name "unconnected-(J4-Pad4)") (class "Default")
      (node (ref "J4") (pin "4") (pinfunction "4_4") (pintype "passive"))
    )
    (net (code "90") (name "unconnected-(J4-Pad8)") (class "Default")
      (node (ref "J4") (pin "8") (pinfunction "8_8") (pintype "passive"))
    )
    (net (code "91") (name "unconnected-(J4-Pad9)") (class "Default")
      (node (ref "J4") (pin "9") (pinfunction "9_9") (pintype "passive"))
    )
    (net (code "92") (name "unconnected-(J4-Pad10)") (class "Default")
      (node (ref "J4") (pin "10") (pinfunction "10_10") (pintype "passive"))
    )
    (net (code "93") (name "unconnected-(J4-Pad11)") (class "Default")
      (node (ref "J4") (pin "11") (pinfunction "11_11") (pintype "passive"))
    )
    (net (code "94") (name "unconnected-(J4-Pad12)") (class "Default")
      (node (ref "J4") (pin "12") (pinfunction "12_12") (pintype "passive"))
    )
    (net (code "95") (name "unconnected-(J14-Pad4)") (class "Default")
      (node (ref "J14") (pin "4") (pinfunction "4_4") (pintype "passive"))
    )
    (net (code "96") (name "unconnected-(J14-Pad8)") (class "Default")
      (node (ref "J14") (pin "8") (pinfunction "8_8") (pintype "passive"))
    )
    (net (code "97") (name "unconnected-(J18-Pad4)") (class "Default")
      (node (ref "J18") (pin "4") (pinfunction "4_4") (pintype "passive"))
    )
    (net (code "98") (name "unconnected-(J18-Pad8)") (class "Default")
      (node (ref "J18") (pin "8") (pinfunction "8_8") (pintype "passive"))
    )
    (net (code "99") (name "unconnected-(SW1-Pad1)") (class "Default")
      (node (ref "SW1") (pin "1") (pinfunction "1_1") (pintype "passive"))
    )
    (net (code "100") (name "unconnected-(SW1-Pad3)") (class "Default")
      (node (ref "SW1") (pin "3") (pinfunction "3_3") (pintype "passive"))
    )
    (net (code "101") (name "unconnected-(U1-1PPS-Pad4)") (class "Default")
      (node (ref "U1") (pin "4") (pinfunction "1PPS_4") (pintype "passive"))
    )
    (net (code "102") (name "unconnected-(U1-ANTON-Pad13)") (class "Default")
      (node (ref "U1") (pin "13") (pinfunction "ANTON_13") (pintype "passive"))
    )
    (net (code "103") (name "unconnected-(U1-NC-Pad7)") (class "Default")
      (node (ref "U1") (pin "7") (pinfunction "NC_7") (pintype "passive"))
    )
    (net (code "104") (name "unconnected-(U1-NC-Pad15)") (class "Default")
      (node (ref "U1") (pin "15") (pinfunction "NC_15") (pintype "passive"))
    )
    (net (code "105") (name "unconnected-(U1-RESRV-Pad16)") (class "Default")
      (node (ref "U1") (pin "16") (pinfunction "RESRV_16") (pintype "passive"))
    )
    (net (code "106") (name "unconnected-(U1-RESRV-Pad17)") (class "Default")
      (node (ref "U1") (pin "17") (pinfunction "RESRV_17") (pintype "passive"))
    )
    (net (code "107") (name "unconnected-(U1-STANDBY-Pad5)") (class "Default")
      (node (ref "U1") (pin "5") (pinfunction "STANDBY_5") (pintype "passive"))
    )
    (net (code "108") (name "unconnected-(U1-VCC_RF-Pad14)") (class "Default")
      (node (ref "U1") (pin "14") (pinfunction "VCC_RF_14") (pintype "passive"))
    )
    (net (code "109") (name "unconnected-(U2-RA4-Pad3)") (class "Default")
      (node (ref "U2") (pin "3") (pinfunction "RA4_3") (pintype "passive"))
    )
    (net (code "110") (name "unconnected-(U2-RA5-Pad2)") (class "Default")
      (node (ref "U2") (pin "2") (pinfunction "RA5_2") (pintype "passive"))
    )
    (net (code "111") (name "unconnected-(U3-1PPS-Pad6)") (class "Default")
      (node (ref "U3") (pin "6") (pinfunction "1PPS_6") (pintype "passive"))
    )
    (net (code "112") (name "unconnected-(U3-AADET_N-Pad8)") (class "Default")
      (node (ref "U3") (pin "8") (pinfunction "AADET_N_8") (pintype "passive"))
    )
    (net (code "113") (name "unconnected-(U3-NC-Pad9)") (class "Default")
      (node (ref "U3") (pin "9") (pinfunction "NC_9") (pintype "passive"))
    )
    (net (code "114") (name "unconnected-(U5B-PCM_CLK-Pad59)") (class "Default")
      (node (ref "U5") (pin "59") (pinfunction "PCM_CLK_59") (pintype "passive"))
    )
    (net (code "115") (name "unconnected-(U5B-PCM_IN-Pad62)") (class "Default")
      (node (ref "U5") (pin "62") (pinfunction "PCM_IN_62") (pintype "passive"))
    )
    (net (code "116") (name "unconnected-(U5B-PCM_OUT-Pad60)") (class "Default")
      (node (ref "U5") (pin "60") (pinfunction "PCM_OUT_60") (pintype "passive"))
    )
    (net (code "117") (name "unconnected-(U5B-PCM_SYNC-Pad61)") (class "Default")
      (node (ref "U5") (pin "61") (pinfunction "PCM_SYNC_61") (pintype "passive"))
    )
    (net (code "118") (name "unconnected-(U5B-RESERVED-Pad55)") (class "Default")
      (node (ref "U5") (pin "55") (pinfunction "RESERVED_55") (pintype "passive"))
    )
    (net (code "119") (name "unconnected-(U5B-RESERVED-Pad56)") (class "Default")
      (node (ref "U5") (pin "56") (pinfunction "RESERVED_56") (pintype "passive"))
    )
    (net (code "120") (name "unconnected-(U5B-RESERVED-Pad57)") (class "Default")
      (node (ref "U5") (pin "57") (pinfunction "RESERVED_57") (pintype "passive"))
    )
    (net (code "121") (name "unconnected-(U5B-RESERVED-Pad58)") (class "Default")
      (node (ref "U5") (pin "58") (pinfunction "RESERVED_58") (pintype "passive"))
    )
    (net (code "122") (name "unconnected-(U5B-RESERVED-Pad63)") (class "Default")
      (node (ref "U5") (pin "63") (pinfunction "RESERVED_63") (pintype "passive"))
    )
    (net (code "123") (name "unconnected-(U5B-RESERVED-Pad64)") (class "Default")
      (node (ref "U5") (pin "64") (pinfunction "RESERVED_64") (pintype "passive"))
    )
    (net (code "124") (name "unconnected-(U5B-RESERVED-Pad65)") (class "Default")
      (node (ref "U5") (pin "65") (pinfunction "RESERVED_65") (pintype "passive"))
    )
    (net (code "125") (name "unconnected-(U5B-RESERVED-Pad66)") (class "Default")
      (node (ref "U5") (pin "66") (pinfunction "RESERVED_66") (pintype "passive"))
    )
    (net (code "126") (name "unconnected-(U5B-RESERVED-Pad67)") (class "Default")
      (node (ref "U5") (pin "67") (pinfunction "RESERVED_67") (pintype "passive"))
    )
    (net (code "127") (name "unconnected-(U5B-RESERVED-Pad68)") (class "Default")
      (node (ref "U5") (pin "68") (pinfunction "RESERVED_68") (pintype "passive"))
    )
  )
)
